# PIR_LedStrip_v1_0.net
KiCad netlist of a schematic drawn in EAGLE
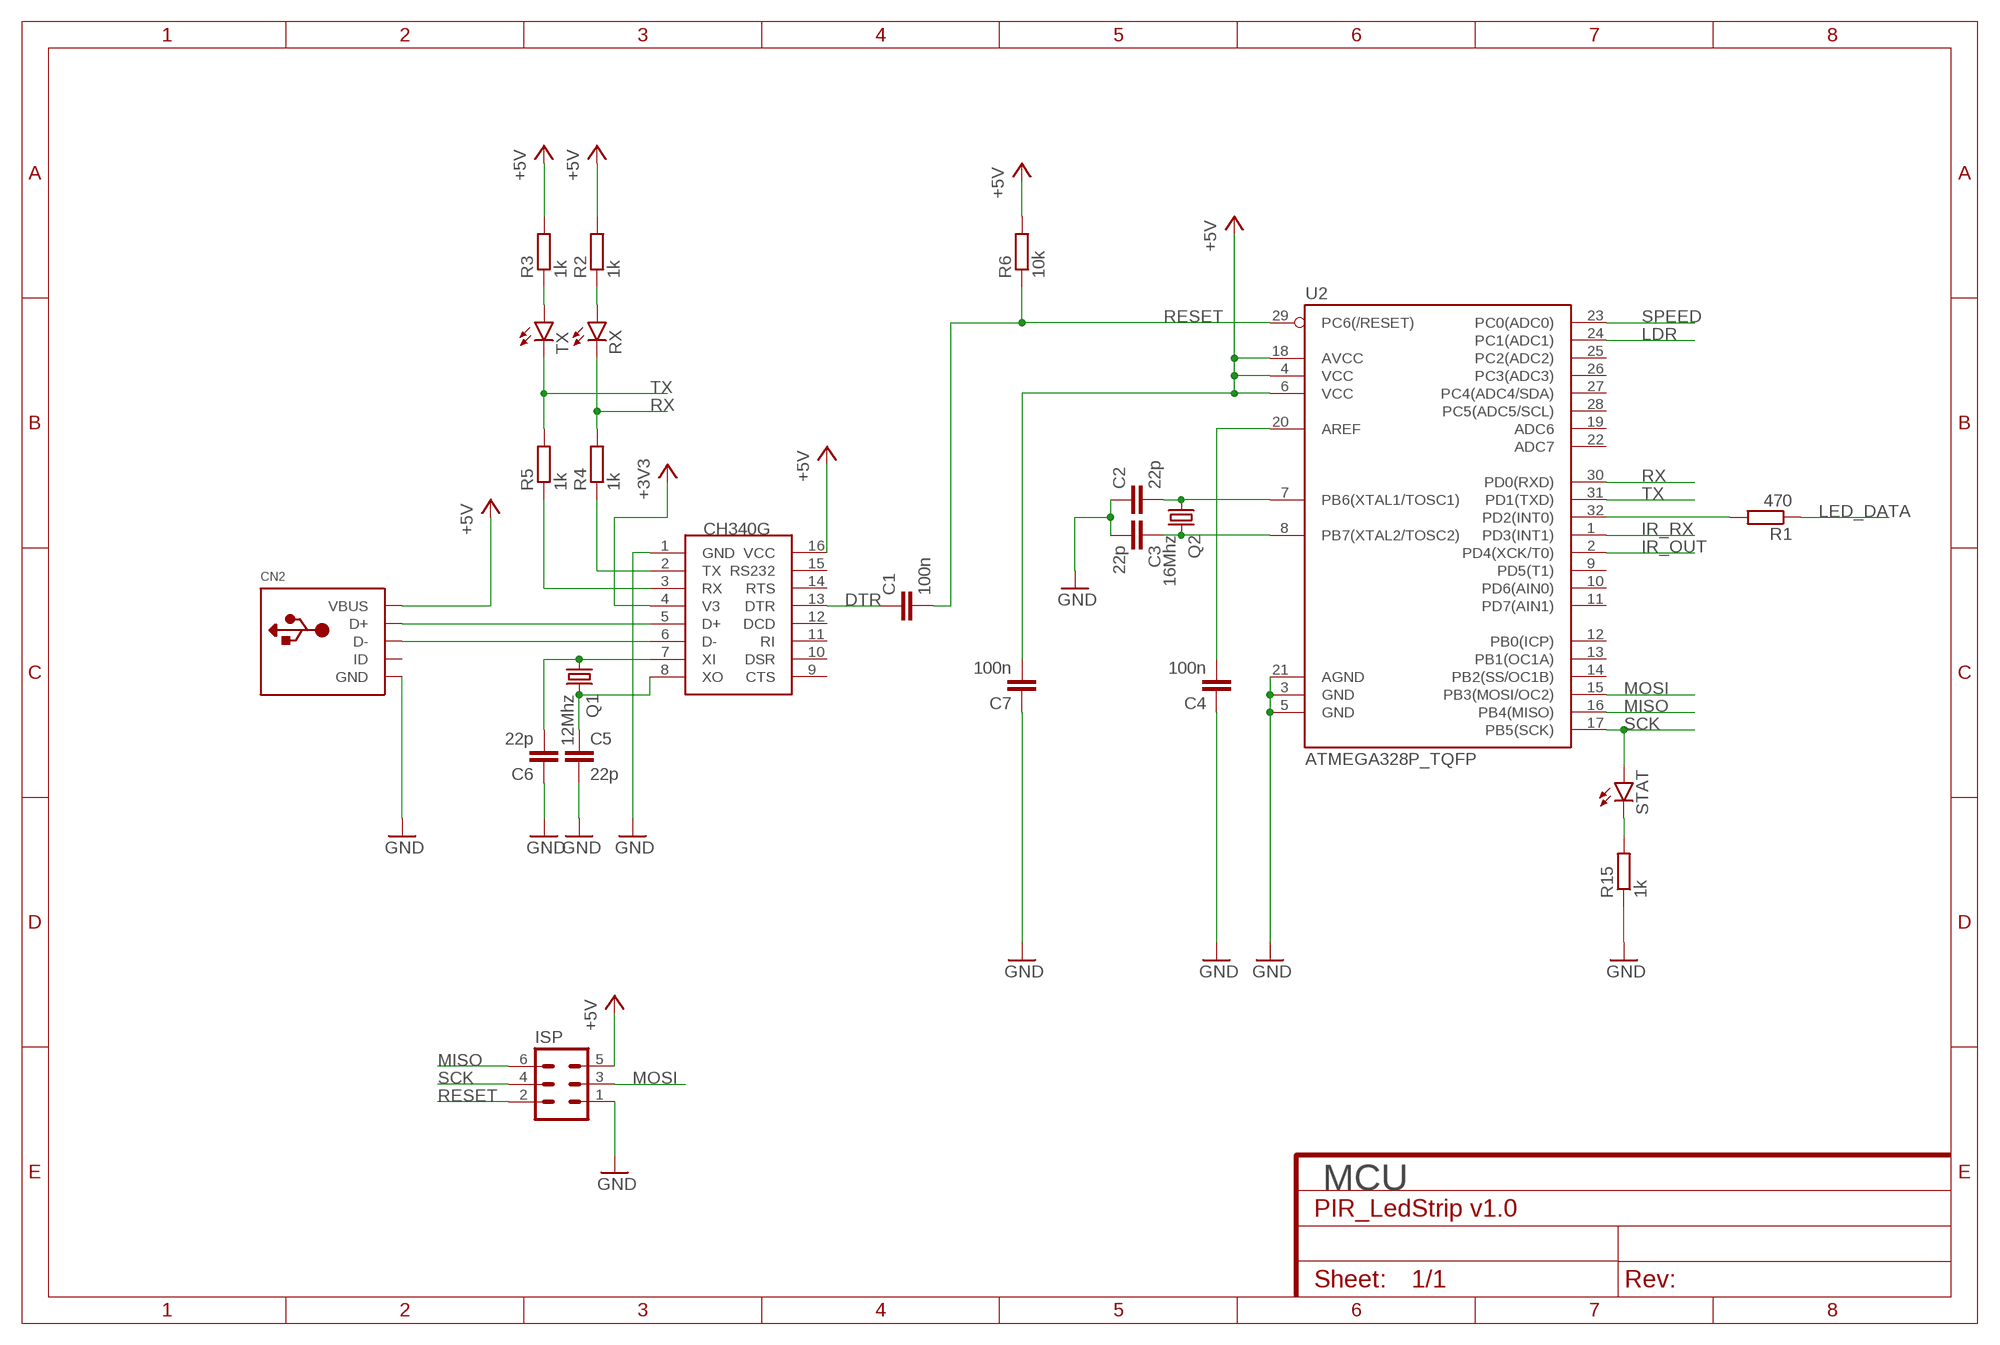
[diagram p0: schematic, sheet 1, part 1 of 2]
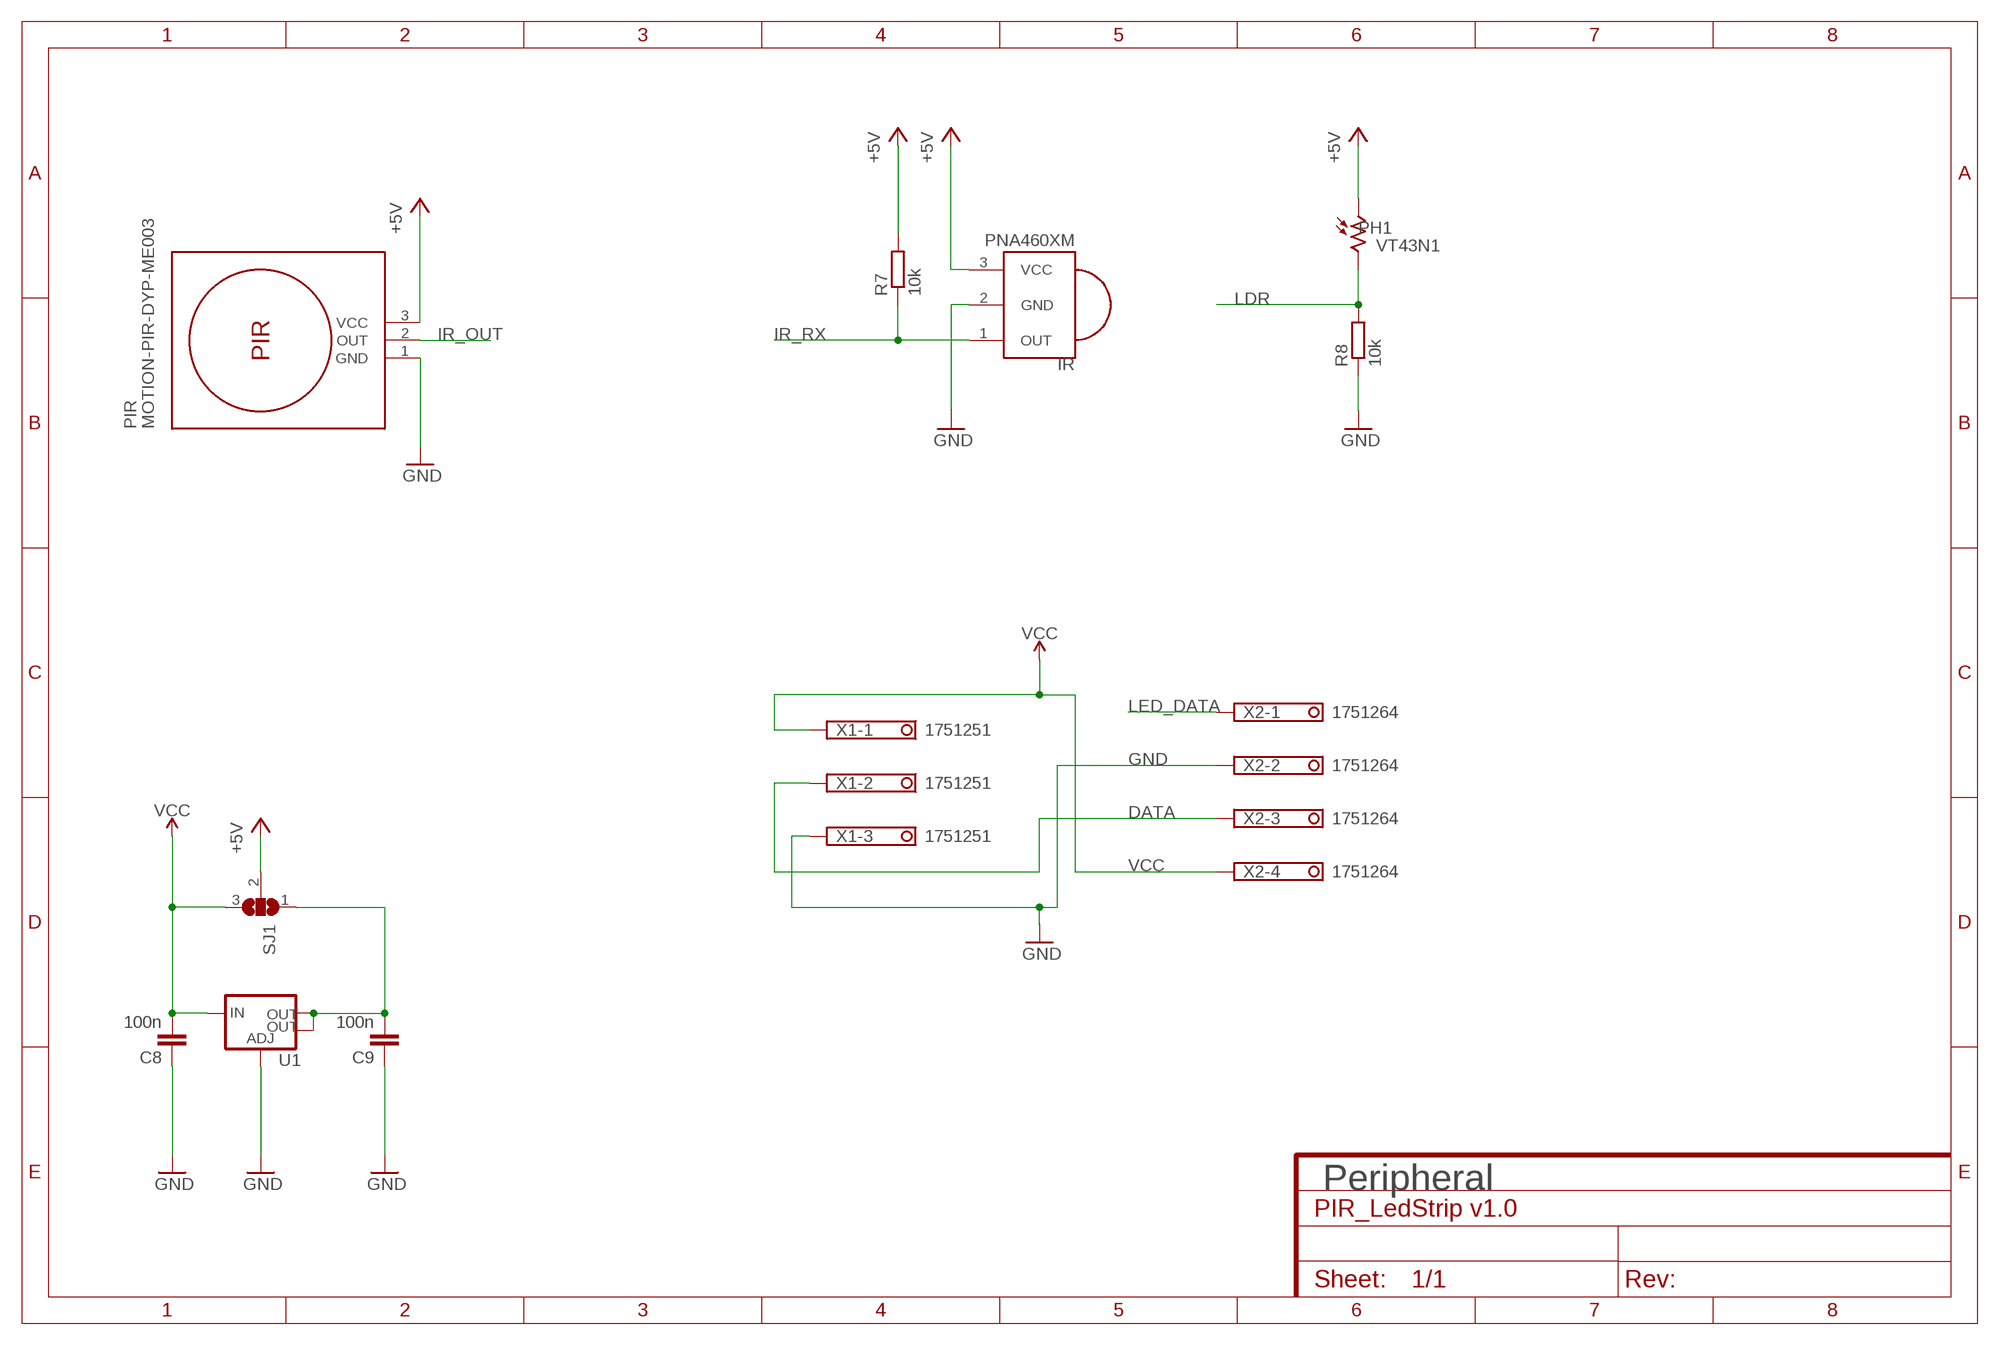
[diagram p1: schematic, sheet 1, part 2 of 2]

(export (version "E")
  (design (tool "Eeschema 10.0.6"))
  (components
    (comp (ref "C1")
      (value "100n")
      (footprint "eagle-import:C0603")
      (libsource (lib "eagle-import") (part "C-EUC0603"))
    )
    (comp (ref "C2")
      (value "22p")
      (footprint "eagle-import:C0603")
      (libsource (lib "eagle-import") (part "C-EUC0603"))
    )
    (comp (ref "C3")
      (value "22p")
      (footprint "eagle-import:C0603")
      (libsource (lib "eagle-import") (part "C-EUC0603"))
    )
    (comp (ref "C4")
      (value "100n")
      (footprint "eagle-import:C0603")
      (libsource (lib "eagle-import") (part "C-EUC0603"))
    )
    (comp (ref "C5")
      (value "22p")
      (footprint "eagle-import:C0603")
      (libsource (lib "eagle-import") (part "C-EUC0603"))
    )
    (comp (ref "C6")
      (value "22p")
      (footprint "eagle-import:C0603")
      (libsource (lib "eagle-import") (part "C-EUC0603"))
    )
    (comp (ref "C7")
      (value "100n")
      (footprint "eagle-import:C0603")
      (libsource (lib "eagle-import") (part "C-EUC0603"))
    )
    (comp (ref "C8")
      (value "100n")
      (footprint "eagle-import:C0603")
      (libsource (lib "eagle-import") (part "C-EUC0603"))
    )
    (comp (ref "C9")
      (value "100n")
      (footprint "eagle-import:C0603")
      (libsource (lib "eagle-import") (part "C-EUC0603"))
    )
    (comp (ref "CN2")
      (value "USBMINIB")
      (footprint "eagle-import:USB-MINIB")
      (libsource (lib "eagle-import") (part "USBMINIB"))
    )
    (comp (ref "IR")
      (value "PNA460XM")
      (footprint "eagle-import:PNA460XM")
      (libsource (lib "eagle-import") (part "PNA460XM"))
    )
    (comp (ref "ISP")
      (value "MA03-2")
      (footprint "eagle-import:MA03-2")
      (libsource (lib "eagle-import") (part "MA03-2"))
    )
    (comp (ref "PH1")
      (value "VT43N1")
      (footprint "eagle-import:VT400")
      (libsource (lib "eagle-import") (part "VT43N1"))
    )
    (comp (ref "PIR")
      (value "MOTION-PIR-DYP-ME003")
      (footprint "eagle-import:MOTION-PIR-DYP-ME003")
      (libsource (lib "eagle-import") (part "MOTION-PIR-DYP-ME003"))
    )
    (comp (ref "Q1")
      (value "12Mhz")
      (footprint "eagle-import:HC49UP")
      (libsource (lib "eagle-import") (part "CRYSTALHC49UP"))
    )
    (comp (ref "Q2")
      (value "16Mhz")
      (footprint "eagle-import:HC49UP")
      (libsource (lib "eagle-import") (part "CRYSTALHC49UP"))
    )
    (comp (ref "R1")
      (value "470")
      (footprint "eagle-import:R0603")
      (libsource (lib "eagle-import") (part "R-EU_R0603"))
    )
    (comp (ref "R2")
      (value "1k")
      (footprint "eagle-import:R0603")
      (libsource (lib "eagle-import") (part "R-EU_R0603"))
    )
    (comp (ref "R3")
      (value "1k")
      (footprint "eagle-import:R0603")
      (libsource (lib "eagle-import") (part "R-EU_R0603"))
    )
    (comp (ref "R4")
      (value "1k")
      (footprint "eagle-import:R0603")
      (libsource (lib "eagle-import") (part "R-EU_R0603"))
    )
    (comp (ref "R5")
      (value "1k")
      (footprint "eagle-import:R0603")
      (libsource (lib "eagle-import") (part "R-EU_R0603"))
    )
    (comp (ref "R6")
      (value "10k")
      (footprint "eagle-import:R0603")
      (libsource (lib "eagle-import") (part "R-EU_R0603"))
    )
    (comp (ref "R7")
      (value "10k")
      (footprint "eagle-import:R0603")
      (libsource (lib "eagle-import") (part "R-EU_R0603"))
    )
    (comp (ref "R8")
      (value "10k")
      (footprint "eagle-import:R0603")
      (libsource (lib "eagle-import") (part "R-EU_R0603"))
    )
    (comp (ref "R15")
      (value "1k")
      (footprint "eagle-import:R0603")
      (libsource (lib "eagle-import") (part "R-EU_R0603"))
    )
    (comp (ref "RX")
      (value "LEDSML0805")
      (footprint "eagle-import:SML0805")
      (libsource (lib "eagle-import") (part "LEDSML0805"))
    )
    (comp (ref "SJ1")
      (value "SJ2W")
      (footprint "eagle-import:SJ_2")
      (libsource (lib "eagle-import") (part "SJ2W"))
    )
    (comp (ref "STAT")
      (value "LEDSML0805")
      (footprint "eagle-import:SML0805")
      (libsource (lib "eagle-import") (part "LEDSML0805"))
    )
    (comp (ref "TX")
      (value "LEDSML0805")
      (footprint "eagle-import:SML0805")
      (libsource (lib "eagle-import") (part "LEDSML0805"))
    )
    (comp (ref "U$1")
      (value "CH340G")
      (footprint "eagle-import:SOIC16")
      (libsource (lib "eagle-import") (part "CH340G"))
    )
    (comp (ref "U1")
      (value "V_REG_LM1117SOT223")
      (footprint "eagle-import:SOT223")
      (libsource (lib "eagle-import") (part "V_REG_LM1117SOT223"))
    )
    (comp (ref "U2")
      (value "ATMEGA328P_TQFP")
      (footprint "eagle-import:TQFP32-08")
      (libsource (lib "eagle-import") (part "ATMEGA328P_TQFP"))
    )
    (comp (ref "X1")
      (value "1751251")
      (footprint "eagle-import:1751251")
      (libsource (lib "eagle-import") (part "1751251"))
    )
    (comp (ref "X2")
      (value "1751264")
      (footprint "eagle-import:1751264")
      (libsource (lib "eagle-import") (part "1751264"))
    )
  )
  (nets
    (net (code "1") (name "+3V3") (class "Default")
      (node (ref "U$1") (pin "4") (pinfunction "V3_4") (pintype "bidirectional"))
    )
    (net (code "2") (name "+5V") (class "Default")
      (node (ref "C7") (pin "2") (pinfunction "2_2") (pintype "passive"))
      (node (ref "CN2") (pin "VBUS") (pinfunction "VBUS_VBUS") (pintype "power_in"))
      (node (ref "IR") (pin "3") (pinfunction "VCC_3") (pintype "power_in"))
      (node (ref "ISP") (pin "5") (pinfunction "5_5") (pintype "passive"))
      (node (ref "PH1") (pin "1") (pinfunction "1_1") (pintype "passive"))
      (node (ref "PIR") (pin "3") (pinfunction "VCC_3") (pintype "power_in"))
      (node (ref "R2") (pin "2") (pinfunction "2_2") (pintype "passive"))
      (node (ref "R3") (pin "2") (pinfunction "2_2") (pintype "passive"))
      (node (ref "R6") (pin "2") (pinfunction "2_2") (pintype "passive"))
      (node (ref "R7") (pin "2") (pinfunction "2_2") (pintype "passive"))
      (node (ref "SJ1") (pin "2") (pinfunction "2_2") (pintype "passive"))
      (node (ref "U$1") (pin "16") (pinfunction "VCC_16") (pintype "bidirectional"))
      (node (ref "U2") (pin "18") (pinfunction "AVCC_18") (pintype "bidirectional"))
      (node (ref "U2") (pin "4") (pinfunction "VCC_4") (pintype "bidirectional"))
      (node (ref "U2") (pin "6") (pinfunction "VCC_6") (pintype "bidirectional"))
    )
    (net (code "3") (name "/DATA") (class "Default")
      (node (ref "X1") (pin "2") (pinfunction "K_2") (pintype "passive"))
      (node (ref "X2") (pin "3") (pinfunction "K_3") (pintype "passive"))
    )
    (net (code "4") (name "/DTR") (class "Default")
      (node (ref "C1") (pin "1") (pinfunction "1_1") (pintype "passive"))
      (node (ref "U$1") (pin "13") (pinfunction "DTR_13") (pintype "bidirectional"))
    )
    (net (code "5") (name "/IR_OUT") (class "Default")
      (node (ref "PIR") (pin "2") (pinfunction "OUT_2") (pintype "output"))
      (node (ref "U2") (pin "2") (pinfunction "PD4(XCK/T0)_2") (pintype "bidirectional"))
    )
    (net (code "6") (name "/IR_RX") (class "Default")
      (node (ref "IR") (pin "1") (pinfunction "OUT_1") (pintype "output"))
      (node (ref "R7") (pin "1") (pinfunction "1_1") (pintype "passive"))
      (node (ref "U2") (pin "1") (pinfunction "PD3(INT1)_1") (pintype "bidirectional"))
    )
    (net (code "7") (name "/LDR") (class "Default")
      (node (ref "PH1") (pin "2") (pinfunction "2_2") (pintype "passive"))
      (node (ref "R8") (pin "2") (pinfunction "2_2") (pintype "passive"))
      (node (ref "U2") (pin "24") (pinfunction "PC1(ADC1)_24") (pintype "bidirectional"))
    )
    (net (code "8") (name "/LED_DATA") (class "Default")
      (node (ref "R1") (pin "1") (pinfunction "1_1") (pintype "passive"))
      (node (ref "X2") (pin "1") (pinfunction "K_1") (pintype "passive"))
    )
    (net (code "9") (name "/MISO") (class "Default")
      (node (ref "ISP") (pin "6") (pinfunction "6_6") (pintype "passive"))
      (node (ref "U2") (pin "16") (pinfunction "PB4(MISO)_16") (pintype "bidirectional"))
    )
    (net (code "10") (name "/MOSI") (class "Default")
      (node (ref "ISP") (pin "3") (pinfunction "3_3") (pintype "passive"))
      (node (ref "U2") (pin "15") (pinfunction "PB3(MOSI/OC2)_15") (pintype "bidirectional"))
    )
    (net (code "11") (name "/RESET") (class "Default")
      (node (ref "C1") (pin "2") (pinfunction "2_2") (pintype "passive"))
      (node (ref "ISP") (pin "2") (pinfunction "2_2") (pintype "passive"))
      (node (ref "R6") (pin "1") (pinfunction "1_1") (pintype "passive"))
      (node (ref "U2") (pin "29") (pinfunction "PC6(/RESET)_29") (pintype "bidirectional"))
    )
    (net (code "12") (name "/RX") (class "Default")
      (node (ref "R4") (pin "2") (pinfunction "2_2") (pintype "passive"))
      (node (ref "RX") (pin "C") (pinfunction "C_C") (pintype "passive"))
      (node (ref "U2") (pin "30") (pinfunction "PD0(RXD)_30") (pintype "bidirectional"))
    )
    (net (code "13") (name "/SCK") (class "Default")
      (node (ref "ISP") (pin "4") (pinfunction "4_4") (pintype "passive"))
      (node (ref "STAT") (pin "A") (pinfunction "A_A") (pintype "passive"))
      (node (ref "U2") (pin "17") (pinfunction "PB5(SCK)_17") (pintype "bidirectional"))
    )
    (net (code "14") (name "/SPEED") (class "Default")
      (node (ref "U2") (pin "23") (pinfunction "PC0(ADC0)_23") (pintype "bidirectional"))
    )
    (net (code "15") (name "/TX") (class "Default")
      (node (ref "R5") (pin "2") (pinfunction "2_2") (pintype "passive"))
      (node (ref "TX") (pin "C") (pinfunction "C_C") (pintype "passive"))
      (node (ref "U2") (pin "31") (pinfunction "PD1(TXD)_31") (pintype "bidirectional"))
    )
    (net (code "16") (name "GND") (class "Default")
      (node (ref "C2") (pin "1") (pinfunction "1_1") (pintype "passive"))
      (node (ref "C3") (pin "2") (pinfunction "2_2") (pintype "passive"))
      (node (ref "C4") (pin "1") (pinfunction "1_1") (pintype "passive"))
      (node (ref "C5") (pin "2") (pinfunction "2_2") (pintype "passive"))
      (node (ref "C6") (pin "1") (pinfunction "1_1") (pintype "passive"))
      (node (ref "C7") (pin "1") (pinfunction "1_1") (pintype "passive"))
      (node (ref "C8") (pin "1") (pinfunction "1_1") (pintype "passive"))
      (node (ref "C9") (pin "1") (pinfunction "1_1") (pintype "passive"))
      (node (ref "CN2") (pin "GND") (pinfunction "GND_GND") (pintype "power_in"))
      (node (ref "IR") (pin "2") (pinfunction "GND_2") (pintype "power_in"))
      (node (ref "ISP") (pin "1") (pinfunction "1_1") (pintype "passive"))
      (node (ref "PIR") (pin "1") (pinfunction "GND_1") (pintype "power_in"))
      (node (ref "R15") (pin "1") (pinfunction "1_1") (pintype "passive"))
      (node (ref "R8") (pin "1") (pinfunction "1_1") (pintype "passive"))
      (node (ref "U$1") (pin "1") (pinfunction "GND_1") (pintype "bidirectional"))
      (node (ref "U1") (pin "1") (pinfunction "ADJ_1") (pintype "input"))
      (node (ref "U2") (pin "21") (pinfunction "AGND_21") (pintype "bidirectional"))
      (node (ref "U2") (pin "3") (pinfunction "GND_3") (pintype "bidirectional"))
      (node (ref "U2") (pin "5") (pinfunction "GND_5") (pintype "bidirectional"))
      (node (ref "X1") (pin "3") (pinfunction "K_3") (pintype "passive"))
      (node (ref "X2") (pin "2") (pinfunction "K_2") (pintype "passive"))
    )
    (net (code "17") (name "Net-(C9-Pad2)") (class "Default")
      (node (ref "C9") (pin "2") (pinfunction "2_2") (pintype "passive"))
      (node (ref "SJ1") (pin "1") (pinfunction "1_1") (pintype "passive"))
      (node (ref "U1") (pin "2") (pinfunction "OUT_2") (pintype "output"))
      (node (ref "U1") (pin "4") (pinfunction "OUT_4") (pintype "output"))
    )
    (net (code "18") (name "Net-(R2-Pad1)") (class "Default")
      (node (ref "R2") (pin "1") (pinfunction "1_1") (pintype "passive"))
      (node (ref "RX") (pin "A") (pinfunction "A_A") (pintype "passive"))
    )
    (net (code "19") (name "Net-(R3-Pad1)") (class "Default")
      (node (ref "R3") (pin "1") (pinfunction "1_1") (pintype "passive"))
      (node (ref "TX") (pin "A") (pinfunction "A_A") (pintype "passive"))
    )
    (net (code "20") (name "Net-(R15-Pad2)") (class "Default")
      (node (ref "R15") (pin "2") (pinfunction "2_2") (pintype "passive"))
      (node (ref "STAT") (pin "C") (pinfunction "C_C") (pintype "passive"))
    )
    (net (code "21") (name "Net-(U$1-D+)") (class "Default")
      (node (ref "CN2") (pin "D+") (pinfunction "D+_D+") (pintype "bidirectional"))
      (node (ref "U$1") (pin "5") (pinfunction "D+_5") (pintype "bidirectional"))
    )
    (net (code "22") (name "Net-(U$1-D-)") (class "Default")
      (node (ref "CN2") (pin "D-") (pinfunction "D-_D-") (pintype "bidirectional"))
      (node (ref "U$1") (pin "6") (pinfunction "D-_6") (pintype "bidirectional"))
    )
    (net (code "23") (name "Net-(U$1-RX)") (class "Default")
      (node (ref "R5") (pin "1") (pinfunction "1_1") (pintype "passive"))
      (node (ref "U$1") (pin "3") (pinfunction "RX_3") (pintype "bidirectional"))
    )
    (net (code "24") (name "Net-(U$1-TX)") (class "Default")
      (node (ref "R4") (pin "1") (pinfunction "1_1") (pintype "passive"))
      (node (ref "U$1") (pin "2") (pinfunction "TX_2") (pintype "bidirectional"))
    )
    (net (code "25") (name "Net-(U$1-XI)") (class "Default")
      (node (ref "C6") (pin "2") (pinfunction "2_2") (pintype "passive"))
      (node (ref "Q1") (pin "1") (pinfunction "1_1") (pintype "passive"))
      (node (ref "U$1") (pin "7") (pinfunction "XI_7") (pintype "bidirectional"))
    )
    (net (code "26") (name "Net-(U$1-XO)") (class "Default")
      (node (ref "C5") (pin "1") (pinfunction "1_1") (pintype "passive"))
      (node (ref "Q1") (pin "2") (pinfunction "2_2") (pintype "passive"))
      (node (ref "U$1") (pin "8") (pinfunction "XO_8") (pintype "bidirectional"))
    )
    (net (code "27") (name "Net-(U2-AREF)") (class "Default")
      (node (ref "C4") (pin "2") (pinfunction "2_2") (pintype "passive"))
      (node (ref "U2") (pin "20") (pinfunction "AREF_20") (pintype "bidirectional"))
    )
    (net (code "28") (name "Net-(U2-PB6(XTAL1{slash}TOSC1))") (class "Default")
      (node (ref "C2") (pin "2") (pinfunction "2_2") (pintype "passive"))
      (node (ref "Q2") (pin "1") (pinfunction "1_1") (pintype "passive"))
      (node (ref "U2") (pin "7") (pinfunction "PB6(XTAL1/TOSC1)_7") (pintype "bidirectional"))
    )
    (net (code "29") (name "Net-(U2-PB7(XTAL2{slash}TOSC2))") (class "Default")
      (node (ref "C3") (pin "1") (pinfunction "1_1") (pintype "passive"))
      (node (ref "Q2") (pin "2") (pinfunction "2_2") (pintype "passive"))
      (node (ref "U2") (pin "8") (pinfunction "PB7(XTAL2/TOSC2)_8") (pintype "bidirectional"))
    )
    (net (code "30") (name "Net-(U2-PD2(INT0))") (class "Default")
      (node (ref "R1") (pin "2") (pinfunction "2_2") (pintype "passive"))
      (node (ref "U2") (pin "32") (pinfunction "PD2(INT0)_32") (pintype "bidirectional"))
    )
    (net (code "31") (name "VCC") (class "Default")
      (node (ref "C8") (pin "2") (pinfunction "2_2") (pintype "passive"))
      (node (ref "SJ1") (pin "3") (pinfunction "3_3") (pintype "passive"))
      (node (ref "U1") (pin "3") (pinfunction "IN_3") (pintype "input"))
      (node (ref "X1") (pin "1") (pinfunction "K_1") (pintype "passive"))
      (node (ref "X2") (pin "4") (pinfunction "K_4") (pintype "passive"))
    )
    (net (code "32") (name "unconnected-(CN2-PadID)") (class "Default")
      (node (ref "CN2") (pin "ID") (pinfunction "ID_ID") (pintype "bidirectional"))
    )
    (net (code "33") (name "unconnected-(U$1-CTS-Pad9)") (class "Default")
      (node (ref "U$1") (pin "9") (pinfunction "CTS_9") (pintype "bidirectional"))
    )
    (net (code "34") (name "unconnected-(U$1-DCD-Pad12)") (class "Default")
      (node (ref "U$1") (pin "12") (pinfunction "DCD_12") (pintype "bidirectional"))
    )
    (net (code "35") (name "unconnected-(U$1-DSR-Pad10)") (class "Default")
      (node (ref "U$1") (pin "10") (pinfunction "DSR_10") (pintype "bidirectional"))
    )
    (net (code "36") (name "unconnected-(U$1-RI-Pad11)") (class "Default")
      (node (ref "U$1") (pin "11") (pinfunction "RI_11") (pintype "bidirectional"))
    )
    (net (code "37") (name "unconnected-(U$1-RS232-Pad15)") (class "Default")
      (node (ref "U$1") (pin "15") (pinfunction "RS232_15") (pintype "bidirectional"))
    )
    (net (code "38") (name "unconnected-(U$1-RTS-Pad14)") (class "Default")
      (node (ref "U$1") (pin "14") (pinfunction "RTS_14") (pintype "bidirectional"))
    )
    (net (code "39") (name "unconnected-(U2-ADC6-Pad19)") (class "Default")
      (node (ref "U2") (pin "19") (pinfunction "ADC6_19") (pintype "bidirectional"))
    )
    (net (code "40") (name "unconnected-(U2-ADC7-Pad22)") (class "Default")
      (node (ref "U2") (pin "22") (pinfunction "ADC7_22") (pintype "bidirectional"))
    )
    (net (code "41") (name "unconnected-(U2-PB0(ICP)-Pad12)") (class "Default")
      (node (ref "U2") (pin "12") (pinfunction "PB0(ICP)_12") (pintype "bidirectional"))
    )
    (net (code "42") (name "unconnected-(U2-PB1(OC1A)-Pad13)") (class "Default")
      (node (ref "U2") (pin "13") (pinfunction "PB1(OC1A)_13") (pintype "bidirectional"))
    )
    (net (code "43") (name "unconnected-(U2-PB2(SS{slash}OC1B)-Pad14)") (class "Default")
      (node (ref "U2") (pin "14") (pinfunction "PB2(SS/OC1B)_14") (pintype "bidirectional"))
    )
    (net (code "44") (name "unconnected-(U2-PC2(ADC2)-Pad25)") (class "Default")
      (node (ref "U2") (pin "25") (pinfunction "PC2(ADC2)_25") (pintype "bidirectional"))
    )
    (net (code "45") (name "unconnected-(U2-PC3(ADC3)-Pad26)") (class "Default")
      (node (ref "U2") (pin "26") (pinfunction "PC3(ADC3)_26") (pintype "bidirectional"))
    )
    (net (code "46") (name "unconnected-(U2-PC4(ADC4{slash}SDA)-Pad27)") (class "Default")
      (node (ref "U2") (pin "27") (pinfunction "PC4(ADC4/SDA)_27") (pintype "bidirectional"))
    )
    (net (code "47") (name "unconnected-(U2-PC5(ADC5{slash}SCL)-Pad28)") (class "Default")
      (node (ref "U2") (pin "28") (pinfunction "PC5(ADC5/SCL)_28") (pintype "bidirectional"))
    )
    (net (code "48") (name "unconnected-(U2-PD5(T1)-Pad9)") (class "Default")
      (node (ref "U2") (pin "9") (pinfunction "PD5(T1)_9") (pintype "bidirectional"))
    )
    (net (code "49") (name "unconnected-(U2-PD6(AIN0)-Pad10)") (class "Default")
      (node (ref "U2") (pin "10") (pinfunction "PD6(AIN0)_10") (pintype "bidirectional"))
    )
    (net (code "50") (name "unconnected-(U2-PD7(AIN1)-Pad11)") (class "Default")
      (node (ref "U2") (pin "11") (pinfunction "PD7(AIN1)_11") (pintype "bidirectional"))
    )
  )
)
